# giraffe_clarity.net
KiCad netlist of a schematic drawn in EAGLE
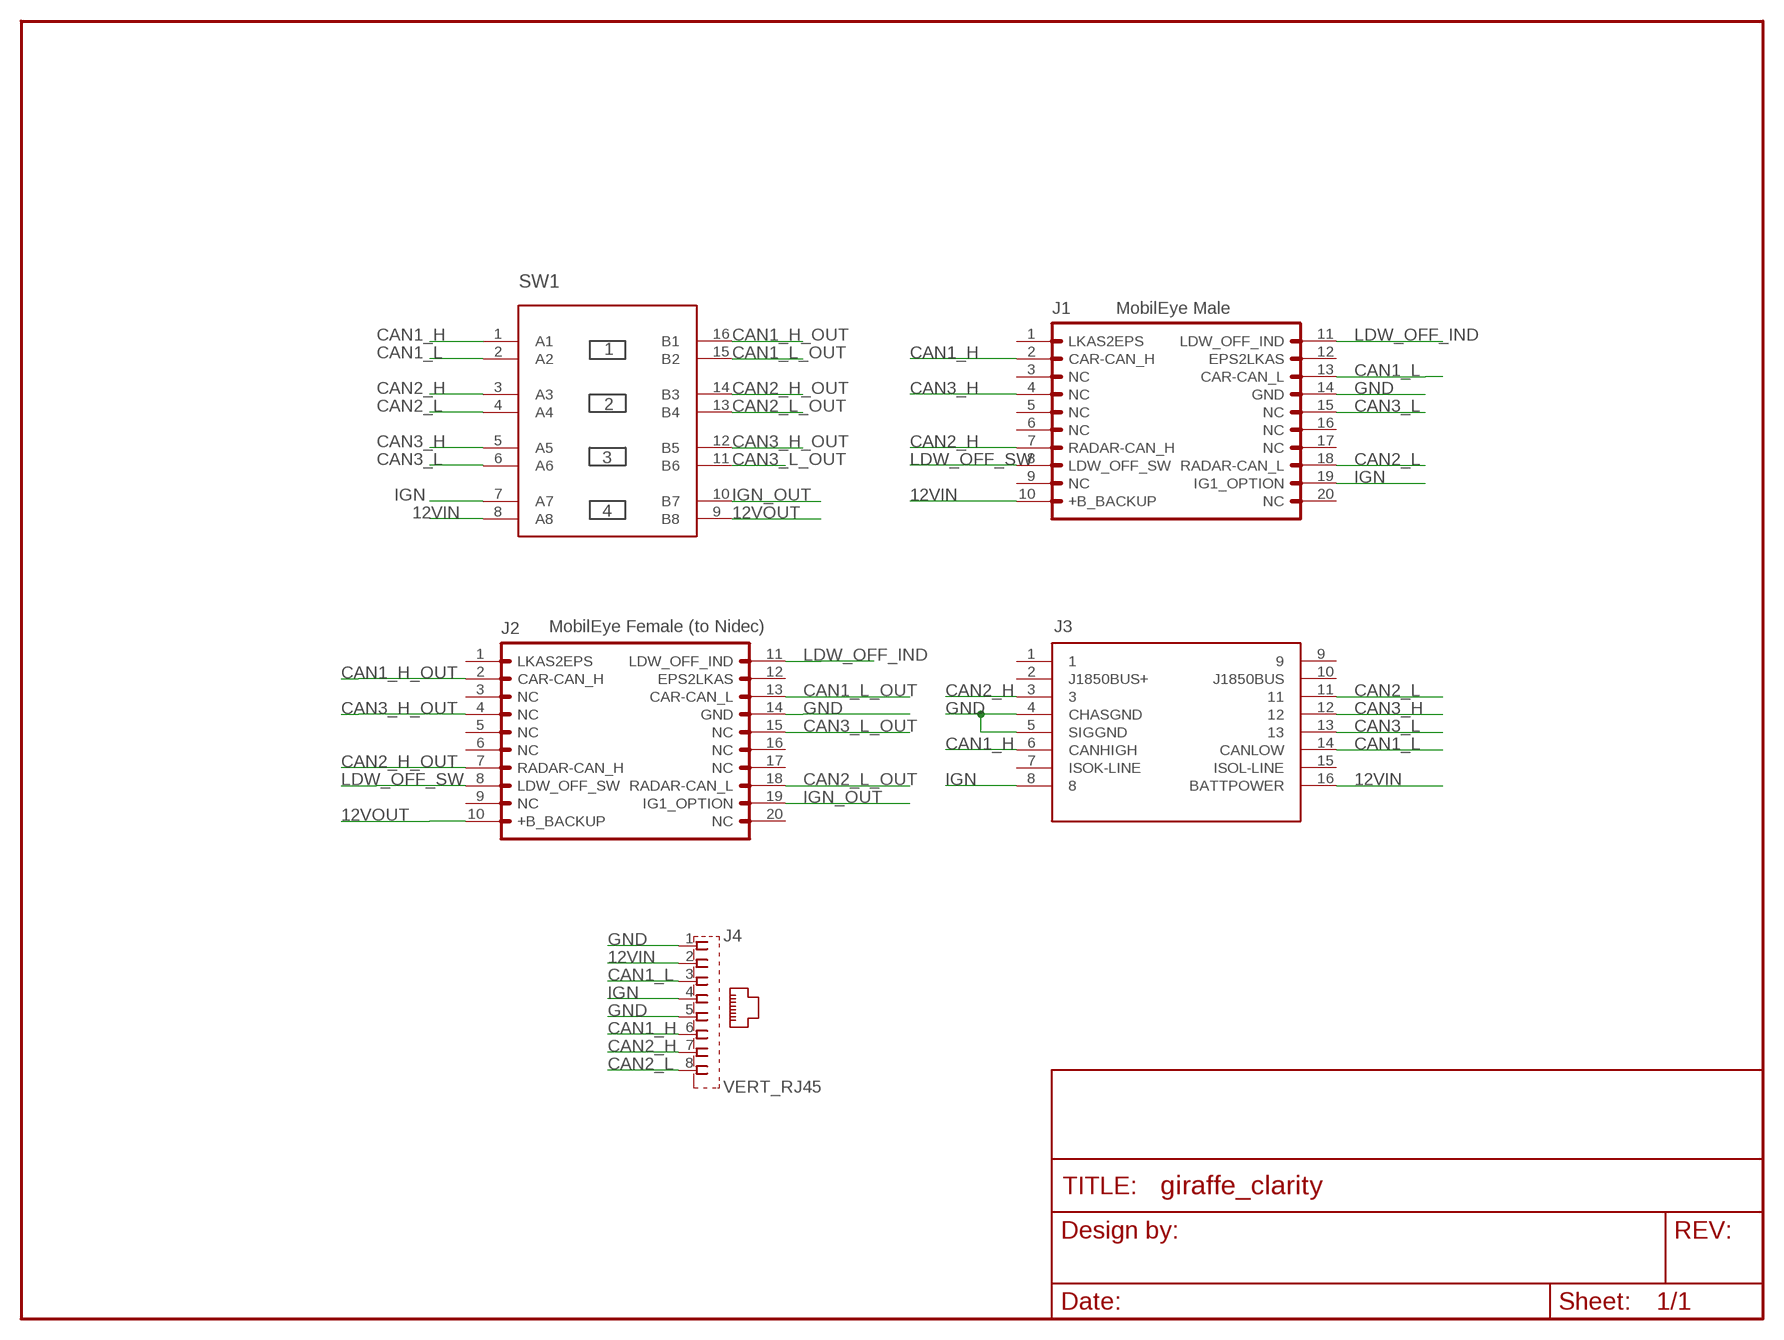
[diagram p0: schematic, sheet 1]

(export (version "E")
  (design (tool "Eeschema 10.0.6"))
  (components
    (comp (ref "FRAME1")
      (value "FRAME-LETTERNO_PACKAGE")
      (footprint "eagle-import:DUMMY")
      (fields (field (name "DESIGNER") "Nobody"))
      (libsource (lib "eagle-import") (part "FRAME-LETTERNO_PACKAGE"))
    )
    (comp (ref "J1")
      (value "MOBILEYERAMALE")
      (footprint "eagle-import:2X10(RA)")
      (libsource (lib "eagle-import") (part "MOBILEYERAMALE"))
    )
    (comp (ref "J2")
      (value "MOBILEYEFEMALE")
      (footprint "eagle-import:2X10(JAE_FEMALE)")
      (libsource (lib "eagle-import") (part "MOBILEYEFEMALE"))
    )
    (comp (ref "J3")
      (value "OBDII-FEMALE-CUT")
      (footprint "eagle-import:OBDII-FEMALE-MIDCUT")
      (libsource (lib "eagle-import") (part "OBDII-FEMALE-CUT"))
    )
    (comp (ref "J4")
      (value "VERT_RJ45")
      (footprint "eagle-import:GLX-S-88M")
      (libsource (lib "eagle-import") (part "VERT_RJ45"))
    )
    (comp (ref "SW1")
      (value "4XDPSTSMT")
      (footprint "eagle-import:4-DPST")
      (libsource (lib "eagle-import") (part "4XDPSTSMT"))
    )
  )
  (nets
    (net (code "1") (name "/12VIN") (class "Default")
      (node (ref "J1") (pin "10") (pinfunction "+B_BACKUP_10") (pintype "bidirectional"))
      (node (ref "J3") (pin "16") (pinfunction "BATTPOWER_16") (pintype "bidirectional"))
      (node (ref "J4") (pin "2") (pinfunction "2_2") (pintype "passive"))
      (node (ref "SW1") (pin "8") (pinfunction "A8_8") (pintype "bidirectional"))
    )
    (net (code "2") (name "/12VOUT") (class "Default")
      (node (ref "J2") (pin "10") (pinfunction "+B_BACKUP_10") (pintype "bidirectional"))
      (node (ref "SW1") (pin "9") (pinfunction "B8_9") (pintype "bidirectional"))
    )
    (net (code "3") (name "/CAN1_H") (class "Default")
      (node (ref "J1") (pin "2") (pinfunction "CAR-CAN_H_2") (pintype "bidirectional"))
      (node (ref "J3") (pin "6") (pinfunction "CANHIGH_6") (pintype "bidirectional"))
      (node (ref "J4") (pin "6") (pinfunction "6_6") (pintype "passive"))
      (node (ref "SW1") (pin "1") (pinfunction "A1_1") (pintype "bidirectional"))
    )
    (net (code "4") (name "/CAN1_H_OUT") (class "Default")
      (node (ref "J2") (pin "2") (pinfunction "CAR-CAN_H_2") (pintype "bidirectional"))
      (node (ref "SW1") (pin "16") (pinfunction "B1_16") (pintype "bidirectional"))
    )
    (net (code "5") (name "/CAN1_L") (class "Default")
      (node (ref "J1") (pin "13") (pinfunction "CAR-CAN_L_13") (pintype "bidirectional"))
      (node (ref "J3") (pin "14") (pinfunction "CANLOW_14") (pintype "bidirectional"))
      (node (ref "J4") (pin "3") (pinfunction "3_3") (pintype "passive"))
      (node (ref "SW1") (pin "2") (pinfunction "A2_2") (pintype "bidirectional"))
    )
    (net (code "6") (name "/CAN1_L_OUT") (class "Default")
      (node (ref "J2") (pin "13") (pinfunction "CAR-CAN_L_13") (pintype "bidirectional"))
      (node (ref "SW1") (pin "15") (pinfunction "B2_15") (pintype "bidirectional"))
    )
    (net (code "7") (name "/CAN2_H") (class "Default")
      (node (ref "J1") (pin "7") (pinfunction "RADAR-CAN_H_7") (pintype "bidirectional"))
      (node (ref "J3") (pin "3") (pinfunction "3_3") (pintype "bidirectional"))
      (node (ref "J4") (pin "7") (pinfunction "7_7") (pintype "passive"))
      (node (ref "SW1") (pin "3") (pinfunction "A3_3") (pintype "bidirectional"))
    )
    (net (code "8") (name "/CAN2_H_OUT") (class "Default")
      (node (ref "J2") (pin "7") (pinfunction "RADAR-CAN_H_7") (pintype "bidirectional"))
      (node (ref "SW1") (pin "14") (pinfunction "B3_14") (pintype "bidirectional"))
    )
    (net (code "9") (name "/CAN2_L") (class "Default")
      (node (ref "J1") (pin "18") (pinfunction "RADAR-CAN_L_18") (pintype "bidirectional"))
      (node (ref "J3") (pin "11") (pinfunction "11_11") (pintype "bidirectional"))
      (node (ref "J4") (pin "8") (pinfunction "8_8") (pintype "passive"))
      (node (ref "SW1") (pin "4") (pinfunction "A4_4") (pintype "bidirectional"))
    )
    (net (code "10") (name "/CAN2_L_OUT") (class "Default")
      (node (ref "J2") (pin "18") (pinfunction "RADAR-CAN_L_18") (pintype "bidirectional"))
      (node (ref "SW1") (pin "13") (pinfunction "B4_13") (pintype "bidirectional"))
    )
    (net (code "11") (name "/CAN3_H") (class "Default")
      (node (ref "J1") (pin "4") (pinfunction "NC_4") (pintype "bidirectional"))
      (node (ref "J3") (pin "12") (pinfunction "12_12") (pintype "bidirectional"))
      (node (ref "SW1") (pin "5") (pinfunction "A5_5") (pintype "bidirectional"))
    )
    (net (code "12") (name "/CAN3_H_OUT") (class "Default")
      (node (ref "J2") (pin "4") (pinfunction "NC_4") (pintype "bidirectional"))
      (node (ref "SW1") (pin "12") (pinfunction "B5_12") (pintype "bidirectional"))
    )
    (net (code "13") (name "/CAN3_L") (class "Default")
      (node (ref "J1") (pin "15") (pinfunction "NC_15") (pintype "bidirectional"))
      (node (ref "J3") (pin "13") (pinfunction "13_13") (pintype "bidirectional"))
      (node (ref "SW1") (pin "6") (pinfunction "A6_6") (pintype "bidirectional"))
    )
    (net (code "14") (name "/CAN3_L_OUT") (class "Default")
      (node (ref "J2") (pin "15") (pinfunction "NC_15") (pintype "bidirectional"))
      (node (ref "SW1") (pin "11") (pinfunction "B6_11") (pintype "bidirectional"))
    )
    (net (code "15") (name "/GND") (class "Default")
      (node (ref "J1") (pin "14") (pinfunction "GND_14") (pintype "bidirectional"))
      (node (ref "J2") (pin "14") (pinfunction "GND_14") (pintype "bidirectional"))
      (node (ref "J3") (pin "4") (pinfunction "CHASGND_4") (pintype "bidirectional"))
      (node (ref "J3") (pin "5") (pinfunction "SIGGND_5") (pintype "bidirectional"))
      (node (ref "J4") (pin "1") (pinfunction "1_1") (pintype "passive"))
      (node (ref "J4") (pin "5") (pinfunction "5_5") (pintype "passive"))
    )
    (net (code "16") (name "/IGN") (class "Default")
      (node (ref "J1") (pin "19") (pinfunction "IG1_OPTION_19") (pintype "bidirectional"))
      (node (ref "J3") (pin "8") (pinfunction "8_8") (pintype "bidirectional"))
      (node (ref "J4") (pin "4") (pinfunction "4_4") (pintype "passive"))
      (node (ref "SW1") (pin "7") (pinfunction "A7_7") (pintype "bidirectional"))
    )
    (net (code "17") (name "/IGN_OUT") (class "Default")
      (node (ref "J2") (pin "19") (pinfunction "IG1_OPTION_19") (pintype "bidirectional"))
      (node (ref "SW1") (pin "10") (pinfunction "B7_10") (pintype "bidirectional"))
    )
    (net (code "18") (name "/LDW_OFF_IND") (class "Default")
      (node (ref "J1") (pin "11") (pinfunction "LDW_OFF_IND_11") (pintype "bidirectional"))
      (node (ref "J2") (pin "11") (pinfunction "LDW_OFF_IND_11") (pintype "bidirectional"))
    )
    (net (code "19") (name "/LDW_OFF_SW") (class "Default")
      (node (ref "J1") (pin "8") (pinfunction "LDW_OFF_SW_8") (pintype "bidirectional"))
      (node (ref "J2") (pin "8") (pinfunction "LDW_OFF_SW_8") (pintype "bidirectional"))
    )
    (net (code "20") (name "unconnected-(J1-EPS2LKAS-Pad12)") (class "Default")
      (node (ref "J1") (pin "12") (pinfunction "EPS2LKAS_12") (pintype "bidirectional"))
    )
    (net (code "21") (name "unconnected-(J1-LKAS2EPS-Pad1)") (class "Default")
      (node (ref "J1") (pin "1") (pinfunction "LKAS2EPS_1") (pintype "bidirectional"))
    )
    (net (code "22") (name "unconnected-(J1-NC-Pad3)") (class "Default")
      (node (ref "J1") (pin "3") (pinfunction "NC_3") (pintype "bidirectional"))
    )
    (net (code "23") (name "unconnected-(J1-NC-Pad5)") (class "Default")
      (node (ref "J1") (pin "5") (pinfunction "NC_5") (pintype "bidirectional"))
    )
    (net (code "24") (name "unconnected-(J1-NC-Pad6)") (class "Default")
      (node (ref "J1") (pin "6") (pinfunction "NC_6") (pintype "bidirectional"))
    )
    (net (code "25") (name "unconnected-(J1-NC-Pad9)") (class "Default")
      (node (ref "J1") (pin "9") (pinfunction "NC_9") (pintype "bidirectional"))
    )
    (net (code "26") (name "unconnected-(J1-NC-Pad16)") (class "Default")
      (node (ref "J1") (pin "16") (pinfunction "NC_16") (pintype "bidirectional"))
    )
    (net (code "27") (name "unconnected-(J1-NC-Pad17)") (class "Default")
      (node (ref "J1") (pin "17") (pinfunction "NC_17") (pintype "bidirectional"))
    )
    (net (code "28") (name "unconnected-(J1-NC-Pad20)") (class "Default")
      (node (ref "J1") (pin "20") (pinfunction "NC_20") (pintype "bidirectional"))
    )
    (net (code "29") (name "unconnected-(J2-EPS2LKAS-Pad12)") (class "Default")
      (node (ref "J2") (pin "12") (pinfunction "EPS2LKAS_12") (pintype "bidirectional"))
    )
    (net (code "30") (name "unconnected-(J2-LKAS2EPS-Pad1)") (class "Default")
      (node (ref "J2") (pin "1") (pinfunction "LKAS2EPS_1") (pintype "bidirectional"))
    )
    (net (code "31") (name "unconnected-(J2-NC-Pad3)") (class "Default")
      (node (ref "J2") (pin "3") (pinfunction "NC_3") (pintype "bidirectional"))
    )
    (net (code "32") (name "unconnected-(J2-NC-Pad5)") (class "Default")
      (node (ref "J2") (pin "5") (pinfunction "NC_5") (pintype "bidirectional"))
    )
    (net (code "33") (name "unconnected-(J2-NC-Pad6)") (class "Default")
      (node (ref "J2") (pin "6") (pinfunction "NC_6") (pintype "bidirectional"))
    )
    (net (code "34") (name "unconnected-(J2-NC-Pad9)") (class "Default")
      (node (ref "J2") (pin "9") (pinfunction "NC_9") (pintype "bidirectional"))
    )
    (net (code "35") (name "unconnected-(J2-NC-Pad16)") (class "Default")
      (node (ref "J2") (pin "16") (pinfunction "NC_16") (pintype "bidirectional"))
    )
    (net (code "36") (name "unconnected-(J2-NC-Pad17)") (class "Default")
      (node (ref "J2") (pin "17") (pinfunction "NC_17") (pintype "bidirectional"))
    )
    (net (code "37") (name "unconnected-(J2-NC-Pad20)") (class "Default")
      (node (ref "J2") (pin "20") (pinfunction "NC_20") (pintype "bidirectional"))
    )
    (net (code "38") (name "unconnected-(J3-ISOK-LINE-Pad7)") (class "Default")
      (node (ref "J3") (pin "7") (pinfunction "ISOK-LINE_7") (pintype "bidirectional"))
    )
    (net (code "39") (name "unconnected-(J3-ISOL-LINE-Pad15)") (class "Default")
      (node (ref "J3") (pin "15") (pinfunction "ISOL-LINE_15") (pintype "bidirectional"))
    )
    (net (code "40") (name "unconnected-(J3-J1850BUS+-Pad2)") (class "Default")
      (node (ref "J3") (pin "2") (pinfunction "J1850BUS+_2") (pintype "bidirectional"))
    )
    (net (code "41") (name "unconnected-(J3-J1850BUS-Pad10)") (class "Default")
      (node (ref "J3") (pin "10") (pinfunction "J1850BUS_10") (pintype "bidirectional"))
    )
    (net (code "42") (name "unconnected-(J3-Pad1)") (class "Default")
      (node (ref "J3") (pin "1") (pinfunction "1_1") (pintype "bidirectional"))
    )
    (net (code "43") (name "unconnected-(J3-Pad9)") (class "Default")
      (node (ref "J3") (pin "9") (pinfunction "9_9") (pintype "bidirectional"))
    )
  )
)
